# sch.net
KiCad netlist of a schematic drawn in Altium Designer
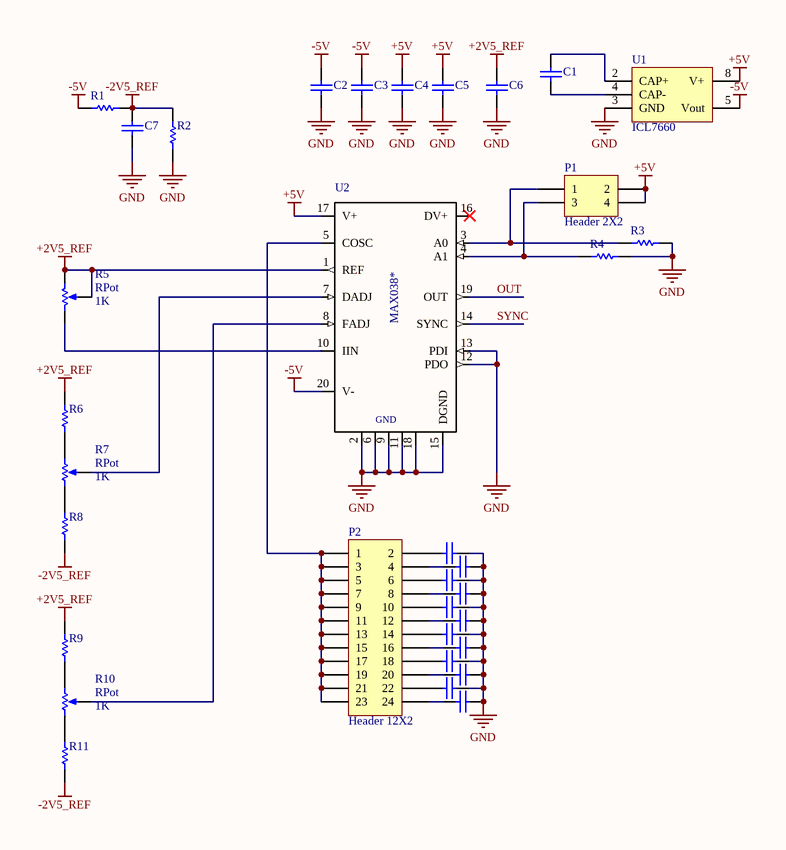
[diagram p0: sch.SchDoc]

(export (version "E")
  (design (tool "Eeschema 10.0.6"))
  (components
    (comp (ref "C1")
      (value "4700pF 100V")
      (footprint "RC_0805_T1.1")
      (description "CAPACITOR CHIP")
      (fields (field (name "MANUFACTURER") "AVX Corporation"))
      (libsource (lib "RozumLibrary") (part "CAP-0805-472-100V"))
    )
    (comp (ref "C2")
      (value "4700pF 100V")
      (footprint "RC_0805_T1.1")
      (description "CAPACITOR CHIP")
      (fields (field (name "MANUFACTURER") "AVX Corporation"))
      (libsource (lib "RozumLibrary") (part "CAP-0805-472-100V"))
    )
    (comp (ref "C3")
      (value "4700pF 100V")
      (footprint "RC_0805_T1.1")
      (description "CAPACITOR CHIP")
      (fields (field (name "MANUFACTURER") "AVX Corporation"))
      (libsource (lib "RozumLibrary") (part "CAP-0805-472-100V"))
    )
    (comp (ref "C4")
      (value "4700pF 100V")
      (footprint "RC_0805_T1.1")
      (description "CAPACITOR CHIP")
      (fields (field (name "MANUFACTURER") "AVX Corporation"))
      (libsource (lib "RozumLibrary") (part "CAP-0805-472-100V"))
    )
    (comp (ref "C5")
      (value "4700pF 100V")
      (footprint "RC_0805_T1.1")
      (description "CAPACITOR CHIP")
      (fields (field (name "MANUFACTURER") "AVX Corporation"))
      (libsource (lib "RozumLibrary") (part "CAP-0805-472-100V"))
    )
    (comp (ref "C6")
      (value "4700pF 100V")
      (footprint "RC_0805_T1.1")
      (description "CAPACITOR CHIP")
      (fields (field (name "MANUFACTURER") "AVX Corporation"))
      (libsource (lib "RozumLibrary") (part "CAP-0805-472-100V"))
    )
    (comp (ref "C7")
      (value "4700pF 100V")
      (footprint "RC_0805_T1.1")
      (description "CAPACITOR CHIP")
      (fields (field (name "MANUFACTURER") "AVX Corporation"))
      (libsource (lib "RozumLibrary") (part "CAP-0805-472-100V"))
    )
    (comp (ref "C8")
      (value "Cap")
      (footprint "RC_0805_T0.8")
      (description "Capacitor")
      (fields (field (name "PUBLISHER") "Altium Limited"))
      (libsource (lib "Miscellaneous Devices") (part "Cap"))
    )
    (comp (ref "C9")
      (value "Cap")
      (footprint "RC_0805_T0.8")
      (description "Capacitor")
      (fields (field (name "PUBLISHER") "Altium Limited"))
      (libsource (lib "Miscellaneous Devices") (part "Cap"))
    )
    (comp (ref "C10")
      (value "Cap")
      (footprint "RC_0805_T0.8")
      (description "Capacitor")
      (fields (field (name "PUBLISHER") "Altium Limited"))
      (libsource (lib "Miscellaneous Devices") (part "Cap"))
    )
    (comp (ref "C11")
      (value "Cap")
      (footprint "RC_0805_T0.8")
      (description "Capacitor")
      (fields (field (name "PUBLISHER") "Altium Limited"))
      (libsource (lib "Miscellaneous Devices") (part "Cap"))
    )
    (comp (ref "C12")
      (value "Cap")
      (footprint "RC_0805_T0.8")
      (description "Capacitor")
      (fields (field (name "PUBLISHER") "Altium Limited"))
      (libsource (lib "Miscellaneous Devices") (part "Cap"))
    )
    (comp (ref "C13")
      (value "Cap")
      (footprint "RC_0805_T0.8")
      (description "Capacitor")
      (fields (field (name "PUBLISHER") "Altium Limited"))
      (libsource (lib "Miscellaneous Devices") (part "Cap"))
    )
    (comp (ref "C14")
      (value "Cap")
      (footprint "RC_0805_T0.8")
      (description "Capacitor")
      (fields (field (name "PUBLISHER") "Altium Limited"))
      (libsource (lib "Miscellaneous Devices") (part "Cap"))
    )
    (comp (ref "C15")
      (value "Cap")
      (footprint "RC_0805_T0.8")
      (description "Capacitor")
      (fields (field (name "PUBLISHER") "Altium Limited"))
      (libsource (lib "Miscellaneous Devices") (part "Cap"))
    )
    (comp (ref "C16")
      (value "Cap")
      (footprint "RC_0805_T0.8")
      (description "Capacitor")
      (fields (field (name "PUBLISHER") "Altium Limited"))
      (libsource (lib "Miscellaneous Devices") (part "Cap"))
    )
    (comp (ref "C17")
      (value "Cap")
      (footprint "RC_0805_T0.8")
      (description "Capacitor")
      (fields (field (name "PUBLISHER") "Altium Limited"))
      (libsource (lib "Miscellaneous Devices") (part "Cap"))
    )
    (comp (ref "C18")
      (value "Cap")
      (footprint "RC_0805_T0.8")
      (description "Capacitor")
      (fields (field (name "PUBLISHER") "Altium Limited"))
      (libsource (lib "Miscellaneous Devices") (part "Cap"))
    )
    (comp (ref "C19")
      (value "Cap")
      (footprint "RC_0805_T0.8")
      (description "Capacitor")
      (fields (field (name "PUBLISHER") "Altium Limited"))
      (libsource (lib "Miscellaneous Devices") (part "Cap"))
    )
    (comp (ref "P1")
      (value "Header 2X2")
      (footprint "HDR2X2")
      (description "Header, 2-Pin, Dual row")
      (fields (field (name "PUBLISHER") "Altium Limited"))
      (libsource (lib "Miscellaneous Connectors") (part "Header 2X2"))
    )
    (comp (ref "P2")
      (value "Header 12X2")
      (footprint "HDR2X12")
      (description "Header, 12-Pin, Dual row")
      (fields (field (name "PUBLISHER") "Altium Limited"))
      (libsource (lib "Miscellaneous Connectors") (part "Header 12X2"))
    )
    (comp (ref "R1")
      (value "~")
      (footprint "RR_0805")
      (description "RESISTOR")
      (fields (field (name "MANUFACTURER") "CAP CER 4700PF 50V X7R 0805"))
      (libsource (lib "RozumLibrary") (part "RES-0805-60R4-0.1%"))
    )
    (comp (ref "R2")
      (value "~")
      (footprint "RR_0805")
      (description "RESISTOR")
      (fields (field (name "MANUFACTURER") "CAP CER 4700PF 50V X7R 0805"))
      (libsource (lib "RozumLibrary") (part "RES-0805-60R4-0.1%"))
    )
    (comp (ref "R3")
      (value "~")
      (footprint "RR_0805")
      (description "RESISTOR")
      (fields (field (name "MANUFACTURER") "CAP CER 4700PF 50V X7R 0805"))
      (libsource (lib "RozumLibrary") (part "RES-0805-60R4-0.1%"))
    )
    (comp (ref "R4")
      (value "~")
      (footprint "RR_0805")
      (description "RESISTOR")
      (fields (field (name "MANUFACTURER") "CAP CER 4700PF 50V X7R 0805"))
      (libsource (lib "RozumLibrary") (part "RES-0805-60R4-0.1%"))
    )
    (comp (ref "R5")
      (value "RPot")
      (footprint "R_POT_16K1")
      (description "Potentiometer")
      (fields (field (name "ALTIUM_VALUE") "1K") (field (name "PUBLISHER") "Altium Limited"))
      (libsource (lib "Miscellaneous Devices") (part "RPot"))
    )
    (comp (ref "R6")
      (value "~")
      (footprint "RR_0805")
      (description "RESISTOR")
      (fields (field (name "MANUFACTURER") "CAP CER 4700PF 50V X7R 0805"))
      (libsource (lib "RozumLibrary") (part "RES-0805-60R4-0.1%"))
    )
    (comp (ref "R7")
      (value "RPot")
      (footprint "R_POT_16K1")
      (description "Potentiometer")
      (fields (field (name "ALTIUM_VALUE") "1K") (field (name "PUBLISHER") "Altium Limited"))
      (libsource (lib "Miscellaneous Devices") (part "RPot"))
    )
    (comp (ref "R8")
      (value "~")
      (footprint "RR_0805")
      (description "RESISTOR")
      (fields (field (name "MANUFACTURER") "CAP CER 4700PF 50V X7R 0805"))
      (libsource (lib "RozumLibrary") (part "RES-0805-60R4-0.1%"))
    )
    (comp (ref "R9")
      (value "~")
      (footprint "RR_0805")
      (description "RESISTOR")
      (fields (field (name "MANUFACTURER") "CAP CER 4700PF 50V X7R 0805"))
      (libsource (lib "RozumLibrary") (part "RES-0805-60R4-0.1%"))
    )
    (comp (ref "R10")
      (value "RPot")
      (footprint "R_POT_16K1")
      (description "Potentiometer")
      (fields (field (name "ALTIUM_VALUE") "1K") (field (name "PUBLISHER") "Altium Limited"))
      (libsource (lib "Miscellaneous Devices") (part "RPot"))
    )
    (comp (ref "R11")
      (value "~")
      (footprint "RR_0805")
      (description "RESISTOR")
      (fields (field (name "MANUFACTURER") "CAP CER 4700PF 50V X7R 0805"))
      (libsource (lib "RozumLibrary") (part "RES-0805-60R4-0.1%"))
    )
    (comp (ref "U1") (value "ICL7660") (footprint "RR_SO-8") (libsource (lib "Schlib1") (part "ICL7660")))
    (comp (ref "U2")
      (value "MAX038*")
      (description "Integrated Circuit")
      (fields (field (name "MP") "MAX038") (field (name "MF") "Maxim Integrated"))
      (libsource (lib "MAX038_") (part "MAX038*"))
    )
  )
  (nets
    (net (code "1") (name "+2V5_REF") (class "Default")
      (node (ref "C6") (pin "2") (pinfunction "2_2") (pintype "passive"))
      (node (ref "R5") (pin "1") (pinfunction "TOP_1") (pintype "passive"))
      (node (ref "R5") (pin "3") (pinfunction "TAP_3") (pintype "passive"))
      (node (ref "R6") (pin "2") (pinfunction "2_2") (pintype "passive"))
      (node (ref "R9") (pin "2") (pinfunction "2_2") (pintype "passive"))
      (node (ref "U2") (pin "1") (pinfunction "REF_1") (pintype "output"))
    )
    (net (code "2") (name "+5V") (class "Default")
      (node (ref "C4") (pin "2") (pinfunction "2_2") (pintype "passive"))
      (node (ref "C5") (pin "2") (pinfunction "2_2") (pintype "passive"))
      (node (ref "P1") (pin "2") (pinfunction "2_2") (pintype "passive"))
      (node (ref "P1") (pin "4") (pinfunction "4_4") (pintype "passive"))
      (node (ref "U1") (pin "8") (pinfunction "V+_8") (pintype "passive"))
      (node (ref "U2") (pin "17") (pinfunction "V+_17") (pintype "power_in"))
    )
    (net (code "3") (name "-2V5_REF") (class "Default")
      (node (ref "C7") (pin "2") (pinfunction "2_2") (pintype "passive"))
      (node (ref "R1") (pin "2") (pinfunction "2_2") (pintype "passive"))
      (node (ref "R11") (pin "1") (pinfunction "1_1") (pintype "passive"))
      (node (ref "R2") (pin "2") (pinfunction "2_2") (pintype "passive"))
      (node (ref "R8") (pin "1") (pinfunction "1_1") (pintype "passive"))
    )
    (net (code "4") (name "-5V") (class "Default")
      (node (ref "C2") (pin "2") (pinfunction "2_2") (pintype "passive"))
      (node (ref "C3") (pin "2") (pinfunction "2_2") (pintype "passive"))
      (node (ref "R1") (pin "1") (pinfunction "1_1") (pintype "passive"))
      (node (ref "U1") (pin "5") (pinfunction "Vout_5") (pintype "passive"))
      (node (ref "U2") (pin "20") (pinfunction "V-_20") (pintype "power_in"))
    )
    (net (code "5") (name "/OUT") (class "Default")
      (node (ref "U2") (pin "19") (pinfunction "OUT_19") (pintype "output"))
    )
    (net (code "6") (name "/SYNC") (class "Default")
      (node (ref "U2") (pin "14") (pinfunction "SYNC_14") (pintype "output"))
    )
    (net (code "7") (name "GND") (class "Default")
      (node (ref "C10") (pin "2") (pinfunction "2_2") (pintype "passive"))
      (node (ref "C11") (pin "2") (pinfunction "2_2") (pintype "passive"))
      (node (ref "C12") (pin "2") (pinfunction "2_2") (pintype "passive"))
      (node (ref "C13") (pin "2") (pinfunction "2_2") (pintype "passive"))
      (node (ref "C14") (pin "2") (pinfunction "2_2") (pintype "passive"))
      (node (ref "C15") (pin "2") (pinfunction "2_2") (pintype "passive"))
      (node (ref "C16") (pin "2") (pinfunction "2_2") (pintype "passive"))
      (node (ref "C17") (pin "2") (pinfunction "2_2") (pintype "passive"))
      (node (ref "C18") (pin "2") (pinfunction "2_2") (pintype "passive"))
      (node (ref "C19") (pin "2") (pinfunction "2_2") (pintype "passive"))
      (node (ref "C2") (pin "1") (pinfunction "1_1") (pintype "passive"))
      (node (ref "C3") (pin "1") (pinfunction "1_1") (pintype "passive"))
      (node (ref "C4") (pin "1") (pinfunction "1_1") (pintype "passive"))
      (node (ref "C5") (pin "1") (pinfunction "1_1") (pintype "passive"))
      (node (ref "C6") (pin "1") (pinfunction "1_1") (pintype "passive"))
      (node (ref "C7") (pin "1") (pinfunction "1_1") (pintype "passive"))
      (node (ref "C8") (pin "2") (pinfunction "2_2") (pintype "passive"))
      (node (ref "C9") (pin "2") (pinfunction "2_2") (pintype "passive"))
      (node (ref "R2") (pin "1") (pinfunction "1_1") (pintype "passive"))
      (node (ref "R3") (pin "2") (pinfunction "2_2") (pintype "passive"))
      (node (ref "R4") (pin "2") (pinfunction "2_2") (pintype "passive"))
      (node (ref "U1") (pin "3") (pinfunction "GND_3") (pintype "passive"))
      (node (ref "U2") (pin "11") (pinfunction "GND@3_11") (pintype "power_in"))
      (node (ref "U2") (pin "12") (pinfunction "PDO_12") (pintype "output"))
      (node (ref "U2") (pin "13") (pinfunction "PDI_13") (pintype "input"))
      (node (ref "U2") (pin "15") (pinfunction "DGND_15") (pintype "power_in"))
      (node (ref "U2") (pin "18") (pinfunction "GND@4_18") (pintype "power_in"))
      (node (ref "U2") (pin "2") (pinfunction "GND_2") (pintype "power_in"))
      (node (ref "U2") (pin "6") (pinfunction "GND@1_6") (pintype "power_in"))
      (node (ref "U2") (pin "9") (pinfunction "GND@2_9") (pintype "power_in"))
    )
    (net (code "8") (name "Net-(C8-Pad1)") (class "Default")
      (node (ref "C8") (pin "1") (pinfunction "1_1") (pintype "passive"))
      (node (ref "P2") (pin "2") (pinfunction "2_2") (pintype "passive"))
    )
    (net (code "9") (name "Net-(C9-Pad1)") (class "Default")
      (node (ref "C9") (pin "1") (pinfunction "1_1") (pintype "passive"))
      (node (ref "P2") (pin "4") (pinfunction "4_4") (pintype "passive"))
    )
    (net (code "10") (name "Net-(C10-Pad1)") (class "Default")
      (node (ref "C10") (pin "1") (pinfunction "1_1") (pintype "passive"))
      (node (ref "P2") (pin "6") (pinfunction "6_6") (pintype "passive"))
    )
    (net (code "11") (name "Net-(C11-Pad1)") (class "Default")
      (node (ref "C11") (pin "1") (pinfunction "1_1") (pintype "passive"))
      (node (ref "P2") (pin "8") (pinfunction "8_8") (pintype "passive"))
    )
    (net (code "12") (name "Net-(C12-Pad1)") (class "Default")
      (node (ref "C12") (pin "1") (pinfunction "1_1") (pintype "passive"))
      (node (ref "P2") (pin "10") (pinfunction "10_10") (pintype "passive"))
    )
    (net (code "13") (name "Net-(C13-Pad1)") (class "Default")
      (node (ref "C13") (pin "1") (pinfunction "1_1") (pintype "passive"))
      (node (ref "P2") (pin "12") (pinfunction "12_12") (pintype "passive"))
    )
    (net (code "14") (name "Net-(C14-Pad1)") (class "Default")
      (node (ref "C14") (pin "1") (pinfunction "1_1") (pintype "passive"))
      (node (ref "P2") (pin "14") (pinfunction "14_14") (pintype "passive"))
    )
    (net (code "15") (name "Net-(C15-Pad1)") (class "Default")
      (node (ref "C15") (pin "1") (pinfunction "1_1") (pintype "passive"))
      (node (ref "P2") (pin "16") (pinfunction "16_16") (pintype "passive"))
    )
    (net (code "16") (name "Net-(C16-Pad1)") (class "Default")
      (node (ref "C16") (pin "1") (pinfunction "1_1") (pintype "passive"))
      (node (ref "P2") (pin "18") (pinfunction "18_18") (pintype "passive"))
    )
    (net (code "17") (name "Net-(C17-Pad1)") (class "Default")
      (node (ref "C17") (pin "1") (pinfunction "1_1") (pintype "passive"))
      (node (ref "P2") (pin "20") (pinfunction "20_20") (pintype "passive"))
    )
    (net (code "18") (name "Net-(C18-Pad1)") (class "Default")
      (node (ref "C18") (pin "1") (pinfunction "1_1") (pintype "passive"))
      (node (ref "P2") (pin "22") (pinfunction "22_22") (pintype "passive"))
    )
    (net (code "19") (name "Net-(C19-Pad1)") (class "Default")
      (node (ref "C19") (pin "1") (pinfunction "1_1") (pintype "passive"))
      (node (ref "P2") (pin "24") (pinfunction "24_24") (pintype "passive"))
    )
    (net (code "20") (name "Net-(R5-BOT)") (class "Default")
      (node (ref "R5") (pin "2") (pinfunction "BOT_2") (pintype "passive"))
      (node (ref "U2") (pin "10") (pinfunction "IIN_10") (pintype "passive"))
    )
    (net (code "21") (name "Net-(R7-BOT)") (class "Default")
      (node (ref "R6") (pin "1") (pinfunction "1_1") (pintype "passive"))
      (node (ref "R7") (pin "2") (pinfunction "BOT_2") (pintype "passive"))
    )
    (net (code "22") (name "Net-(R7-TAP)") (class "Default")
      (node (ref "R7") (pin "3") (pinfunction "TAP_3") (pintype "passive"))
      (node (ref "U2") (pin "7") (pinfunction "DADJ_7") (pintype "input"))
    )
    (net (code "23") (name "Net-(R7-TOP)") (class "Default")
      (node (ref "R7") (pin "1") (pinfunction "TOP_1") (pintype "passive"))
      (node (ref "R8") (pin "2") (pinfunction "2_2") (pintype "passive"))
    )
    (net (code "24") (name "Net-(R10-BOT)") (class "Default")
      (node (ref "R10") (pin "2") (pinfunction "BOT_2") (pintype "passive"))
      (node (ref "R9") (pin "1") (pinfunction "1_1") (pintype "passive"))
    )
    (net (code "25") (name "Net-(R10-TAP)") (class "Default")
      (node (ref "R10") (pin "3") (pinfunction "TAP_3") (pintype "passive"))
      (node (ref "U2") (pin "8") (pinfunction "FADJ_8") (pintype "input"))
    )
    (net (code "26") (name "Net-(R10-TOP)") (class "Default")
      (node (ref "R10") (pin "1") (pinfunction "TOP_1") (pintype "passive"))
      (node (ref "R11") (pin "2") (pinfunction "2_2") (pintype "passive"))
    )
    (net (code "27") (name "Net-(U1-CAP+)") (class "Default")
      (node (ref "C1") (pin "2") (pinfunction "2_2") (pintype "passive"))
      (node (ref "U1") (pin "2") (pinfunction "CAP+_2") (pintype "passive"))
    )
    (net (code "28") (name "Net-(U1-CAP-)") (class "Default")
      (node (ref "C1") (pin "1") (pinfunction "1_1") (pintype "passive"))
      (node (ref "U1") (pin "4") (pinfunction "CAP-_4") (pintype "passive"))
    )
    (net (code "29") (name "Net-(U2-A0)") (class "Default")
      (node (ref "P1") (pin "1") (pinfunction "1_1") (pintype "passive"))
      (node (ref "R3") (pin "1") (pinfunction "1_1") (pintype "passive"))
      (node (ref "U2") (pin "3") (pinfunction "A0_3") (pintype "input"))
    )
    (net (code "30") (name "Net-(U2-A1)") (class "Default")
      (node (ref "P1") (pin "3") (pinfunction "3_3") (pintype "passive"))
      (node (ref "R4") (pin "1") (pinfunction "1_1") (pintype "passive"))
      (node (ref "U2") (pin "4") (pinfunction "A1_4") (pintype "input"))
    )
    (net (code "31") (name "Net-(U2-COSC)") (class "Default")
      (node (ref "P2") (pin "1") (pinfunction "1_1") (pintype "passive"))
      (node (ref "P2") (pin "11") (pinfunction "11_11") (pintype "passive"))
      (node (ref "P2") (pin "13") (pinfunction "13_13") (pintype "passive"))
      (node (ref "P2") (pin "15") (pinfunction "15_15") (pintype "passive"))
      (node (ref "P2") (pin "17") (pinfunction "17_17") (pintype "passive"))
      (node (ref "P2") (pin "19") (pinfunction "19_19") (pintype "passive"))
      (node (ref "P2") (pin "21") (pinfunction "21_21") (pintype "passive"))
      (node (ref "P2") (pin "23") (pinfunction "23_23") (pintype "passive"))
      (node (ref "P2") (pin "3") (pinfunction "3_3") (pintype "passive"))
      (node (ref "P2") (pin "5") (pinfunction "5_5") (pintype "passive"))
      (node (ref "P2") (pin "7") (pinfunction "7_7") (pintype "passive"))
      (node (ref "P2") (pin "9") (pinfunction "9_9") (pintype "passive"))
      (node (ref "U2") (pin "5") (pinfunction "COSC_5") (pintype "passive"))
    )
    (net (code "32") (name "unconnected-(U2-DV+-Pad16)") (class "Default")
      (node (ref "U2") (pin "16") (pinfunction "DV+_16") (pintype "power_in+no_connect"))
    )
  )
)
